# 05_-_POWER.net
KiCad netlist of a schematic drawn in Altium Designer
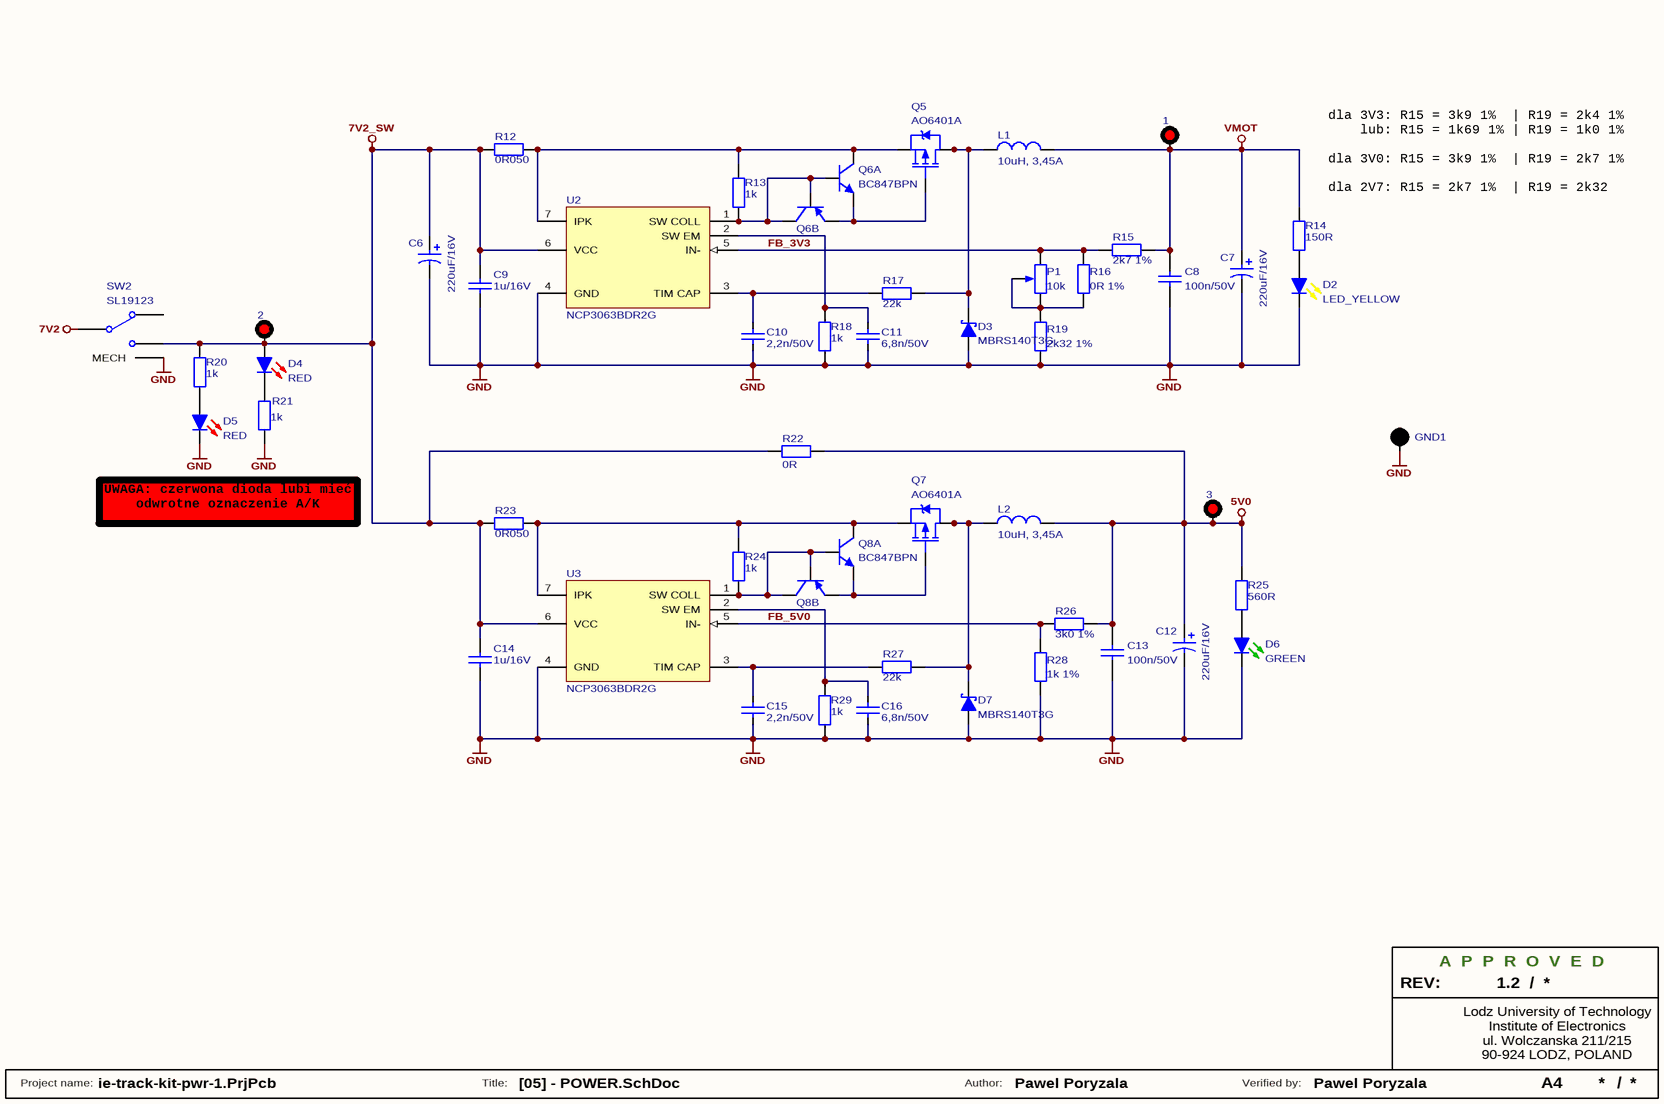
[diagram p0: [05] - POWER.SchDoc]

(export (version "E")
  (design (tool "Eeschema 10.0.6"))
  (components
    (comp (ref "1")
      (value "Keystone 5000 Test Point (RED)")
      (footprint "Keystone_5000_RED")
      (libsource (lib "test_points") (part "Keystone 5000 Test Point"))
    )
    (comp (ref "2")
      (value "Keystone 5000 Test Point (RED)")
      (footprint "Keystone_5000_RED")
      (libsource (lib "test_points") (part "Keystone 5000 Test Point"))
    )
    (comp (ref "3")
      (value "Keystone 5000 Test Point (RED)")
      (footprint "Keystone_5000_RED")
      (libsource (lib "test_points") (part "Keystone 5000 Test Point"))
    )
    (comp (ref "C6")
      (value "220uF/16V")
      (footprint "CES_E_8.3x8.3_6.2")
      (description "Polarized Capacitor")
      (libsource (lib "capacitors") (part "Cap Pol"))
    )
    (comp (ref "C7")
      (value "220uF/16V")
      (footprint "CES_E_8.3x8.3_6.2")
      (description "Polarized Capacitor")
      (libsource (lib "capacitors") (part "Cap Pol"))
    )
    (comp (ref "C8")
      (value "100n/50V")
      (footprint "C0805")
      (description "Capacitor")
      (libsource (lib "capacitors") (part "Cap"))
    )
    (comp (ref "C9")
      (value "1u/16V")
      (footprint "C0805")
      (description "Capacitor")
      (libsource (lib "") (part "Cap_2"))
    )
    (comp (ref "C10")
      (value "2,2n/50V")
      (footprint "C0805")
      (description "Capacitor")
      (libsource (lib "") (part "Cap_1"))
    )
    (comp (ref "C11")
      (value "6,8n/50V")
      (footprint "C0805")
      (description "Capacitor")
      (libsource (lib "") (part "Cap_1"))
    )
    (comp (ref "C12")
      (value "220uF/16V")
      (footprint "CES_E_8.3x8.3_6.2")
      (description "Polarized Capacitor")
      (libsource (lib "capacitors") (part "Cap Pol"))
    )
    (comp (ref "C13")
      (value "100n/50V")
      (footprint "C0805")
      (description "Capacitor")
      (libsource (lib "capacitors") (part "Cap"))
    )
    (comp (ref "C14")
      (value "1u/16V")
      (footprint "C0805")
      (description "Capacitor")
      (libsource (lib "") (part "Cap_2"))
    )
    (comp (ref "C15")
      (value "2,2n/50V")
      (footprint "C0805")
      (description "Capacitor")
      (libsource (lib "") (part "Cap_1"))
    )
    (comp (ref "C16")
      (value "6,8n/50V")
      (footprint "C0805")
      (description "Capacitor")
      (libsource (lib "") (part "Cap_1"))
    )
    (comp (ref "D2")
      (value "LED_YELLOW")
      (footprint "LED0805Y")
      (description "YELLOW LED")
      (libsource (lib "leds") (part "LED_YELLOW"))
    )
    (comp (ref "D3")
      (value "MBRS140T3G")
      (footprint "SMB")
      (description "Schottky barrier rectifier: 40V, 1A")
      (libsource (lib "diodes_schottky") (part "MBRS140T3G"))
    )
    (comp (ref "D4")
      (value "RED")
      (footprint "LED0805R")
      (description "RED LED")
      (libsource (lib "leds") (part "LED_RED"))
    )
    (comp (ref "D5")
      (value "RED")
      (footprint "LED0805R")
      (description "RED LED")
      (libsource (lib "leds") (part "LED_RED"))
    )
    (comp (ref "D6")
      (value "GREEN")
      (footprint "LED0805G")
      (description "GREEN LED")
      (libsource (lib "leds") (part "LED_GREEN"))
    )
    (comp (ref "D7")
      (value "MBRS140T3G")
      (footprint "SMB")
      (description "Schottky barrier rectifier: 40V, 1A")
      (libsource (lib "diodes_schottky") (part "MBRS140T3G"))
    )
    (comp (ref "GND1")
      (value "Keystone 5001 Test Point (BLACK)")
      (footprint "Keystone_5001_BLACK")
      (libsource (lib "test_points") (part "Keystone 5001 Test Point"))
    )
    (comp (ref "L1")
      (value "10uH, 3,45A")
      (footprint "PSDB1005")
      (description "10uH, 20%, 3,45A, PSDB1005N Series Inductor")
      (libsource (lib "inductors") (part "PSDB1005NT100"))
    )
    (comp (ref "L2")
      (value "10uH, 3,45A")
      (footprint "PSDB1005")
      (description "10uH, 20%, 3,45A, PSDB1005N Series Inductor")
      (libsource (lib "inductors") (part "PSDB1005NT100"))
    )
    (comp (ref "P1")
      (value "10k")
      (footprint "3364W")
      (description "3364W-1-103E")
      (libsource (lib "resistors") (part "3364W-1-103E"))
    )
    (comp (ref "Q5")
      (value "AO6401A")
      (footprint "SOT-23-6")
      (description "P-Channel MOSFET; -60V, -5A, 1.3W;")
      (libsource (lib "transistors_mos") (part "AO6401A"))
    )
    (comp (ref "Q6")
      (value "BC847BPN")
      (footprint "SOT-323-6 (SOT-363, SC88, SC70-6)")
      (description "PNP/NPN General Purpose Transistor (VCE=45V, IC=100mA)")
      (libsource (lib "transistors_bjt") (part "BC847BPN"))
    )
    (comp (ref "Q7")
      (value "AO6401A")
      (footprint "SOT-23-6")
      (description "P-Channel MOSFET; -60V, -5A, 1.3W;")
      (libsource (lib "transistors_mos") (part "AO6401A"))
    )
    (comp (ref "Q8")
      (value "BC847BPN")
      (footprint "SOT-323-6 (SOT-363, SC88, SC70-6)")
      (description "PNP/NPN General Purpose Transistor (VCE=45V, IC=100mA)")
      (libsource (lib "transistors_bjt") (part "BC847BPN"))
    )
    (comp (ref "R12")
      (value "0R050")
      (footprint "R0805")
      (description "Resistor")
      (libsource (lib "") (part "Res_2"))
    )
    (comp (ref "R13")
      (value "1k")
      (footprint "R0805")
      (description "Resistor")
      (libsource (lib "") (part "Res_1"))
    )
    (comp (ref "R14")
      (value "150R")
      (footprint "R0805")
      (description "Resistor")
      (libsource (lib "") (part "Res_1"))
    )
    (comp (ref "R15")
      (value "2k7 1%")
      (footprint "R0805")
      (description "Resistor")
      (libsource (lib "") (part "Res_2"))
    )
    (comp (ref "R16")
      (value "0R 1%")
      (footprint "R0805")
      (description "Resistor")
      (libsource (lib "") (part "Res_1"))
    )
    (comp (ref "R17")
      (value "22k")
      (footprint "R0805")
      (description "Resistor")
      (libsource (lib "") (part "Res_3"))
    )
    (comp (ref "R18")
      (value "1k")
      (footprint "R0805")
      (description "Resistor")
      (libsource (lib "") (part "Res_1"))
    )
    (comp (ref "R19")
      (value "2k32 1%")
      (footprint "R0805")
      (description "Resistor")
      (libsource (lib "") (part "Res_1"))
    )
    (comp (ref "R20")
      (value "1k")
      (footprint "R0805")
      (description "Resistor")
      (libsource (lib "") (part "Res_1"))
    )
    (comp (ref "R21")
      (value "1k")
      (footprint "R0805")
      (description "Resistor")
      (libsource (lib "") (part "Res_1"))
    )
    (comp (ref "R22")
      (value "0R")
      (footprint "R1206")
      (description "Resistor")
      (libsource (lib "resistors") (part "Res"))
    )
    (comp (ref "R23")
      (value "0R050")
      (footprint "R0805")
      (description "Resistor")
      (libsource (lib "") (part "Res_2"))
    )
    (comp (ref "R24")
      (value "1k")
      (footprint "R0805")
      (description "Resistor")
      (libsource (lib "") (part "Res_1"))
    )
    (comp (ref "R25")
      (value "560R")
      (footprint "R0805")
      (description "Resistor")
      (libsource (lib "") (part "Res_1"))
    )
    (comp (ref "R26")
      (value "3k0 1%")
      (footprint "R0805")
      (description "Resistor")
      (libsource (lib "") (part "Res_2"))
    )
    (comp (ref "R27")
      (value "22k")
      (footprint "R0805")
      (description "Resistor")
      (libsource (lib "") (part "Res_3"))
    )
    (comp (ref "R28")
      (value "1k 1%")
      (footprint "R0805")
      (description "Resistor")
      (libsource (lib "") (part "Res_1"))
    )
    (comp (ref "R29")
      (value "1k")
      (footprint "R0805")
      (description "Resistor")
      (libsource (lib "") (part "Res_1"))
    )
    (comp (ref "SW2")
      (value "SL19123")
      (footprint "500SSPxS1M6xEA")
      (description "Canal Electronic SPDT AC: 3A/250V, DC: 6A/28V")
      (libsource (lib "switches_slide") (part "SL19123"))
    )
    (comp (ref "U2")
      (value "NCP3063BDR2G")
      (footprint "SO8")
      (description "DC-DC Converter NCP3063BDR2G (Farnell 1547126)")
      (libsource (lib "switched_voltage_regulators") (part "NCP3063BDR2G"))
    )
    (comp (ref "U3")
      (value "NCP3063BDR2G")
      (footprint "SO8")
      (description "DC-DC Converter NCP3063BDR2G (Farnell 1547126)")
      (libsource (lib "switched_voltage_regulators") (part "NCP3063BDR2G"))
    )
  )
  (nets
    (net (code "1") (name "/FB_3V3") (class "Default")
      (node (ref "P1") (pin "1") (pinfunction "TOP_1") (pintype "passive"))
      (node (ref "R15") (pin "1") (pinfunction "1_1") (pintype "passive"))
      (node (ref "R16") (pin "1") (pinfunction "1_1") (pintype "passive"))
      (node (ref "U2") (pin "5") (pinfunction "IN-_5") (pintype "input"))
    )
    (net (code "2") (name "/FB_5V0") (class "Default")
      (node (ref "R26") (pin "1") (pinfunction "1_1") (pintype "passive"))
      (node (ref "R28") (pin "1") (pinfunction "1_1") (pintype "passive"))
      (node (ref "U3") (pin "5") (pinfunction "IN-_5") (pintype "input"))
    )
    (net (code "3") (name "5V0") (class "Default")
      (node (ref "3") (pin "0") (pinfunction "0_0") (pintype "passive"))
      (node (ref "C12") (pin "1") (pinfunction "1_1") (pintype "passive"))
      (node (ref "C13") (pin "2") (pinfunction "2_2") (pintype "passive"))
      (node (ref "L2") (pin "2") (pinfunction "2_2") (pintype "passive"))
      (node (ref "R22") (pin "2") (pinfunction "2_2") (pintype "passive"))
      (node (ref "R25") (pin "1") (pinfunction "1_1") (pintype "passive"))
      (node (ref "R26") (pin "2") (pinfunction "2_2") (pintype "passive"))
    )
    (net (code "4") (name "7V2") (class "Default")
      (node (ref "SW2") (pin "2") (pinfunction "2_2") (pintype "passive"))
    )
    (net (code "5") (name "7V2_SW") (class "Default")
      (node (ref "2") (pin "0") (pinfunction "0_0") (pintype "passive"))
      (node (ref "C14") (pin "2") (pinfunction "2_2") (pintype "passive"))
      (node (ref "C6") (pin "1") (pinfunction "1_1") (pintype "passive"))
      (node (ref "C9") (pin "2") (pinfunction "2_2") (pintype "passive"))
      (node (ref "D4") (pin "1") (pinfunction "A_1") (pintype "passive"))
      (node (ref "R12") (pin "1") (pinfunction "1_1") (pintype "passive"))
      (node (ref "R20") (pin "1") (pinfunction "1_1") (pintype "passive"))
      (node (ref "R22") (pin "1") (pinfunction "1_1") (pintype "passive"))
      (node (ref "R23") (pin "1") (pinfunction "1_1") (pintype "passive"))
      (node (ref "SW2") (pin "3") (pinfunction "3_3") (pintype "passive"))
      (node (ref "U2") (pin "6") (pinfunction "VCC_6") (pintype "power_in"))
      (node (ref "U3") (pin "6") (pinfunction "VCC_6") (pintype "power_in"))
    )
    (net (code "6") (name "GND") (class "Default")
      (node (ref "C10") (pin "1") (pinfunction "1_1") (pintype "passive"))
      (node (ref "C11") (pin "1") (pinfunction "1_1") (pintype "passive"))
      (node (ref "C12") (pin "2") (pinfunction "2_2") (pintype "passive"))
      (node (ref "C13") (pin "1") (pinfunction "1_1") (pintype "passive"))
      (node (ref "C14") (pin "1") (pinfunction "1_1") (pintype "passive"))
      (node (ref "C15") (pin "1") (pinfunction "1_1") (pintype "passive"))
      (node (ref "C16") (pin "1") (pinfunction "1_1") (pintype "passive"))
      (node (ref "C6") (pin "2") (pinfunction "2_2") (pintype "passive"))
      (node (ref "C7") (pin "2") (pinfunction "2_2") (pintype "passive"))
      (node (ref "C8") (pin "1") (pinfunction "1_1") (pintype "passive"))
      (node (ref "C9") (pin "1") (pinfunction "1_1") (pintype "passive"))
      (node (ref "D2") (pin "2") (pinfunction "K_2") (pintype "passive"))
      (node (ref "D3") (pin "1") (pinfunction "A_1") (pintype "passive"))
      (node (ref "D5") (pin "2") (pinfunction "K_2") (pintype "passive"))
      (node (ref "D6") (pin "2") (pinfunction "K_2") (pintype "passive"))
      (node (ref "D7") (pin "1") (pinfunction "A_1") (pintype "passive"))
      (node (ref "GND1") (pin "0") (pinfunction "0_0") (pintype "passive"))
      (node (ref "R18") (pin "2") (pinfunction "2_2") (pintype "passive"))
      (node (ref "R19") (pin "2") (pinfunction "2_2") (pintype "passive"))
      (node (ref "R21") (pin "2") (pinfunction "2_2") (pintype "passive"))
      (node (ref "R28") (pin "2") (pinfunction "2_2") (pintype "passive"))
      (node (ref "R29") (pin "2") (pinfunction "2_2") (pintype "passive"))
      (node (ref "SW2") (pin "M") (pinfunction "MECH_M") (pintype "passive"))
      (node (ref "U2") (pin "4") (pinfunction "GND_4") (pintype "power_in"))
      (node (ref "U3") (pin "4") (pinfunction "GND_4") (pintype "power_in"))
    )
    (net (code "7") (name "Net-(D2-A)") (class "Default")
      (node (ref "D2") (pin "1") (pinfunction "A_1") (pintype "passive"))
      (node (ref "R14") (pin "2") (pinfunction "2_2") (pintype "passive"))
    )
    (net (code "8") (name "Net-(D3-K)") (class "Default")
      (node (ref "D3") (pin "2") (pinfunction "K_2") (pintype "passive"))
      (node (ref "L1") (pin "1") (pinfunction "1_1") (pintype "passive"))
      (node (ref "Q5") (pin "1") (pinfunction "D_1") (pintype "passive"))
      (node (ref "Q5") (pin "2") (pinfunction "D_2") (pintype "passive"))
      (node (ref "Q5") (pin "5") (pinfunction "D_5") (pintype "passive"))
      (node (ref "Q5") (pin "6") (pinfunction "D_6") (pintype "passive"))
      (node (ref "R17") (pin "1") (pinfunction "1_1") (pintype "passive"))
    )
    (net (code "9") (name "Net-(D4-K)") (class "Default")
      (node (ref "D4") (pin "2") (pinfunction "K_2") (pintype "passive"))
      (node (ref "R21") (pin "1") (pinfunction "1_1") (pintype "passive"))
    )
    (net (code "10") (name "Net-(D5-A)") (class "Default")
      (node (ref "D5") (pin "1") (pinfunction "A_1") (pintype "passive"))
      (node (ref "R20") (pin "2") (pinfunction "2_2") (pintype "passive"))
    )
    (net (code "11") (name "Net-(D6-A)") (class "Default")
      (node (ref "D6") (pin "1") (pinfunction "A_1") (pintype "passive"))
      (node (ref "R25") (pin "2") (pinfunction "2_2") (pintype "passive"))
    )
    (net (code "12") (name "Net-(D7-K)") (class "Default")
      (node (ref "D7") (pin "2") (pinfunction "K_2") (pintype "passive"))
      (node (ref "L2") (pin "1") (pinfunction "1_1") (pintype "passive"))
      (node (ref "Q7") (pin "1") (pinfunction "D_1") (pintype "passive"))
      (node (ref "Q7") (pin "2") (pinfunction "D_2") (pintype "passive"))
      (node (ref "Q7") (pin "5") (pinfunction "D_5") (pintype "passive"))
      (node (ref "Q7") (pin "6") (pinfunction "D_6") (pintype "passive"))
      (node (ref "R27") (pin "1") (pinfunction "1_1") (pintype "passive"))
    )
    (net (code "13") (name "Net-(P1-BOT)") (class "Default")
      (node (ref "P1") (pin "2") (pinfunction "BOT_2") (pintype "passive"))
      (node (ref "P1") (pin "3") (pinfunction "TAP_3") (pintype "passive"))
      (node (ref "R16") (pin "2") (pinfunction "2_2") (pintype "passive"))
      (node (ref "R19") (pin "1") (pinfunction "1_1") (pintype "passive"))
    )
    (net (code "14") (name "Net-(Q5-G)") (class "Default")
      (node (ref "Q5") (pin "3") (pinfunction "G_3") (pintype "passive"))
      (node (ref "Q6") (pin "1") (pinfunction "EA_1") (pintype "passive"))
      (node (ref "Q6") (pin "4") (pinfunction "EB_4") (pintype "passive"))
    )
    (net (code "15") (name "Net-(Q5-S)") (class "Default")
      (node (ref "Q5") (pin "4") (pinfunction "S_4") (pintype "passive"))
      (node (ref "Q6") (pin "6") (pinfunction "CA_6") (pintype "passive"))
      (node (ref "R12") (pin "2") (pinfunction "2_2") (pintype "passive"))
      (node (ref "R13") (pin "1") (pinfunction "1_1") (pintype "passive"))
      (node (ref "U2") (pin "7") (pinfunction "IPK_7") (pintype "passive"))
    )
    (net (code "16") (name "Net-(Q6A-BA)") (class "Default")
      (node (ref "Q6") (pin "2") (pinfunction "BA_2") (pintype "passive"))
      (node (ref "Q6") (pin "3") (pinfunction "CB_3") (pintype "passive"))
      (node (ref "Q6") (pin "5") (pinfunction "BB_5") (pintype "passive"))
      (node (ref "R13") (pin "2") (pinfunction "2_2") (pintype "passive"))
      (node (ref "U2") (pin "1") (pinfunction "SW_COLL_1") (pintype "passive"))
    )
    (net (code "17") (name "Net-(Q7-G)") (class "Default")
      (node (ref "Q7") (pin "3") (pinfunction "G_3") (pintype "passive"))
      (node (ref "Q8") (pin "1") (pinfunction "EA_1") (pintype "passive"))
      (node (ref "Q8") (pin "4") (pinfunction "EB_4") (pintype "passive"))
    )
    (net (code "18") (name "Net-(Q7-S)") (class "Default")
      (node (ref "Q7") (pin "4") (pinfunction "S_4") (pintype "passive"))
      (node (ref "Q8") (pin "6") (pinfunction "CA_6") (pintype "passive"))
      (node (ref "R23") (pin "2") (pinfunction "2_2") (pintype "passive"))
      (node (ref "R24") (pin "1") (pinfunction "1_1") (pintype "passive"))
      (node (ref "U3") (pin "7") (pinfunction "IPK_7") (pintype "passive"))
    )
    (net (code "19") (name "Net-(Q8A-BA)") (class "Default")
      (node (ref "Q8") (pin "2") (pinfunction "BA_2") (pintype "passive"))
      (node (ref "Q8") (pin "3") (pinfunction "CB_3") (pintype "passive"))
      (node (ref "Q8") (pin "5") (pinfunction "BB_5") (pintype "passive"))
      (node (ref "R24") (pin "2") (pinfunction "2_2") (pintype "passive"))
      (node (ref "U3") (pin "1") (pinfunction "SW_COLL_1") (pintype "passive"))
    )
    (net (code "20") (name "Net-(U2-SW_EM)") (class "Default")
      (node (ref "C11") (pin "2") (pinfunction "2_2") (pintype "passive"))
      (node (ref "R18") (pin "1") (pinfunction "1_1") (pintype "passive"))
      (node (ref "U2") (pin "2") (pinfunction "SW_EM_2") (pintype "passive"))
    )
    (net (code "21") (name "Net-(U2-TIM_CAP)") (class "Default")
      (node (ref "C10") (pin "2") (pinfunction "2_2") (pintype "passive"))
      (node (ref "R17") (pin "2") (pinfunction "2_2") (pintype "passive"))
      (node (ref "U2") (pin "3") (pinfunction "TIM_CAP_3") (pintype "passive"))
    )
    (net (code "22") (name "Net-(U3-SW_EM)") (class "Default")
      (node (ref "C16") (pin "2") (pinfunction "2_2") (pintype "passive"))
      (node (ref "R29") (pin "1") (pinfunction "1_1") (pintype "passive"))
      (node (ref "U3") (pin "2") (pinfunction "SW_EM_2") (pintype "passive"))
    )
    (net (code "23") (name "Net-(U3-TIM_CAP)") (class "Default")
      (node (ref "C15") (pin "2") (pinfunction "2_2") (pintype "passive"))
      (node (ref "R27") (pin "2") (pinfunction "2_2") (pintype "passive"))
      (node (ref "U3") (pin "3") (pinfunction "TIM_CAP_3") (pintype "passive"))
    )
    (net (code "24") (name "VMOT") (class "Default")
      (node (ref "1") (pin "0") (pinfunction "0_0") (pintype "passive"))
      (node (ref "C7") (pin "1") (pinfunction "1_1") (pintype "passive"))
      (node (ref "C8") (pin "2") (pinfunction "2_2") (pintype "passive"))
      (node (ref "L1") (pin "2") (pinfunction "2_2") (pintype "passive"))
      (node (ref "R14") (pin "1") (pinfunction "1_1") (pintype "passive"))
      (node (ref "R15") (pin "2") (pinfunction "2_2") (pintype "passive"))
    )
    (net (code "25") (name "unconnected-(SW2-Pad1)") (class "Default")
      (node (ref "SW2") (pin "1") (pinfunction "1_1") (pintype "passive"))
    )
  )
)
